# aasaver_v11.net
KiCad netlist of a schematic drawn in EAGLE
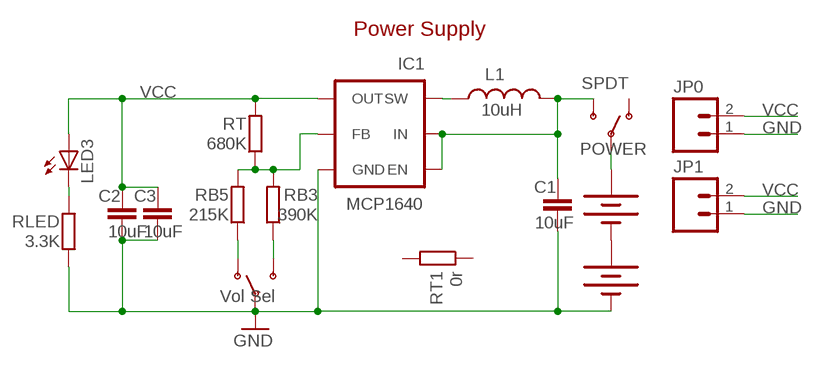
[diagram p0: schematic, sheet 1]

(export (version "E")
  (design (tool "Eeschema 10.0.6"))
  (components
    (comp (ref "AA1")
      (value "BATTERYAA")
      (footprint "eagle-import:BATTERY-AA")
      (libsource (lib "eagle-import") (part "BATTERYAA"))
    )
    (comp (ref "AA2")
      (value "BATTERYAA")
      (footprint "eagle-import:BATTERY-AA")
      (libsource (lib "eagle-import") (part "BATTERYAA"))
    )
    (comp (ref "C1")
      (value "10uF")
      (footprint "eagle-import:C0805")
      (libsource (lib "eagle-import") (part "C-EUC0805"))
    )
    (comp (ref "C2")
      (value "10uF")
      (footprint "eagle-import:C0805")
      (libsource (lib "eagle-import") (part "C-EUC0805"))
    )
    (comp (ref "C3")
      (value "10uF")
      (footprint "eagle-import:C0805")
      (libsource (lib "eagle-import") (part "C-EUC0805"))
    )
    (comp (ref "IC1")
      (value "MCP1640")
      (footprint "eagle-import:TSOT23-6")
      (libsource (lib "eagle-import") (part "MCP1640"))
    )
    (comp (ref "JP0")
      (value "M021X02_NO_SILK")
      (footprint "eagle-import:1X02_NO_SILK")
      (libsource (lib "eagle-import") (part "M021X02_NO_SILK"))
    )
    (comp (ref "JP1")
      (value "M021X02_NO_SILK")
      (footprint "eagle-import:1X02_NO_SILK")
      (libsource (lib "eagle-import") (part "M021X02_NO_SILK"))
    )
    (comp (ref "L1")
      (value "10uH")
      (footprint "eagle-import:INDUCTOR_D45")
      (libsource (lib "eagle-import") (part "INDUCTOR_SMDD45"))
    )
    (comp (ref "LED3")
      (value "0805")
      (footprint "eagle-import:CHIPLED_1206")
      (libsource (lib "eagle-import") (part "LEDCHIPLED_1206"))
    )
    (comp (ref "POWER")
      (value "SPDT")
      (footprint "eagle-import:SWITCH-SPDT-SMD")
      (libsource (lib "eagle-import") (part "SWITCH-SPSTSMD2"))
    )
    (comp (ref "RB3")
      (value "390K")
      (footprint "eagle-import:R0805")
      (libsource (lib "eagle-import") (part "R-EU_R0805"))
    )
    (comp (ref "RB5")
      (value "215K")
      (footprint "eagle-import:R0805")
      (libsource (lib "eagle-import") (part "R-EU_R0805"))
    )
    (comp (ref "RLED")
      (value "3.3K")
      (footprint "eagle-import:R0805")
      (libsource (lib "eagle-import") (part "R-EU_R0805"))
    )
    (comp (ref "RT")
      (value "680K")
      (footprint "eagle-import:R0805")
      (libsource (lib "eagle-import") (part "R-EU_R0805"))
    )
    (comp (ref "RT1")
      (value "0r")
      (footprint "eagle-import:R1206")
      (libsource (lib "eagle-import") (part "R-EU_R1206"))
    )
    (comp (ref "VOL1")
      (value "Vol Sel")
      (footprint "eagle-import:SWITCH-SPDT-SMD")
      (libsource (lib "eagle-import") (part "SWITCH-SPSTSMD2"))
    )
  )
  (nets
    (net (code "1") (name "/VCC") (class "Default")
      (node (ref "C2") (pin "1") (pinfunction "1_1") (pintype "passive"))
      (node (ref "C3") (pin "1") (pinfunction "1_1") (pintype "passive"))
      (node (ref "IC1") (pin "5") (pinfunction "OUT_5") (pintype "passive"))
      (node (ref "JP0") (pin "2") (pinfunction "2_2") (pintype "passive"))
      (node (ref "JP1") (pin "2") (pinfunction "2_2") (pintype "passive"))
      (node (ref "LED3") (pin "A") (pinfunction "A_A") (pintype "passive"))
      (node (ref "RT") (pin "2") (pinfunction "2_2") (pintype "passive"))
    )
    (net (code "2") (name "GND") (class "Default")
      (node (ref "AA2") (pin "GND@1") (pinfunction "-_GND@1") (pintype "power_in"))
      (node (ref "C1") (pin "2") (pinfunction "2_2") (pintype "passive"))
      (node (ref "C2") (pin "2") (pinfunction "2_2") (pintype "passive"))
      (node (ref "C3") (pin "2") (pinfunction "2_2") (pintype "passive"))
      (node (ref "IC1") (pin "2") (pinfunction "GND_2") (pintype "input"))
      (node (ref "JP0") (pin "1") (pinfunction "1_1") (pintype "passive"))
      (node (ref "JP1") (pin "1") (pinfunction "1_1") (pintype "passive"))
      (node (ref "RLED") (pin "1") (pinfunction "1_1") (pintype "passive"))
      (node (ref "VOL1") (pin "2") (pinfunction "P_2") (pintype "passive"))
    )
    (net (code "3") (name "Net-(AA1-+)") (class "Default")
      (node (ref "AA1") (pin "PWR@1") (pinfunction "+_PWR@1") (pintype "power_in"))
      (node (ref "POWER") (pin "2") (pinfunction "P_2") (pintype "passive"))
    )
    (net (code "4") (name "Net-(AA1--)") (class "Default")
      (node (ref "AA1") (pin "GND@1") (pinfunction "-_GND@1") (pintype "power_in"))
      (node (ref "AA2") (pin "PWR@1") (pinfunction "+_PWR@1") (pintype "power_in"))
    )
    (net (code "5") (name "Net-(IC1-EN)") (class "Default")
      (node (ref "C1") (pin "1") (pinfunction "1_1") (pintype "passive"))
      (node (ref "IC1") (pin "3") (pinfunction "EN_3") (pintype "input"))
      (node (ref "IC1") (pin "6") (pinfunction "IN_6") (pintype "input"))
      (node (ref "L1") (pin "P$1") (pinfunction "1_P$1") (pintype "passive"))
      (node (ref "POWER") (pin "3") (pinfunction "S_3") (pintype "passive"))
    )
    (net (code "6") (name "Net-(IC1-FB)") (class "Default")
      (node (ref "IC1") (pin "4") (pinfunction "FB_4") (pintype "input"))
      (node (ref "RB3") (pin "2") (pinfunction "2_2") (pintype "passive"))
      (node (ref "RB5") (pin "2") (pinfunction "2_2") (pintype "passive"))
      (node (ref "RT") (pin "1") (pinfunction "1_1") (pintype "passive"))
    )
    (net (code "7") (name "Net-(IC1-SW)") (class "Default")
      (node (ref "IC1") (pin "1") (pinfunction "SW_1") (pintype "output"))
      (node (ref "L1") (pin "P$2") (pinfunction "2_P$2") (pintype "passive"))
    )
    (net (code "8") (name "Net-(LED3-PadC)") (class "Default")
      (node (ref "LED3") (pin "C") (pinfunction "C_C") (pintype "passive"))
      (node (ref "RLED") (pin "2") (pinfunction "2_2") (pintype "passive"))
    )
    (net (code "9") (name "Net-(VOL1-O)") (class "Default")
      (node (ref "RB5") (pin "1") (pinfunction "1_1") (pintype "passive"))
      (node (ref "VOL1") (pin "1") (pinfunction "O_1") (pintype "passive"))
    )
    (net (code "10") (name "Net-(VOL1-S)") (class "Default")
      (node (ref "RB3") (pin "1") (pinfunction "1_1") (pintype "passive"))
      (node (ref "VOL1") (pin "3") (pinfunction "S_3") (pintype "passive"))
    )
    (net (code "11") (name "unconnected-(POWER-O-Pad1)") (class "Default")
      (node (ref "POWER") (pin "1") (pinfunction "O_1") (pintype "passive"))
    )
    (net (code "12") (name "unconnected-(RT1-Pad1)") (class "Default")
      (node (ref "RT1") (pin "1") (pinfunction "1_1") (pintype "passive"))
    )
    (net (code "13") (name "unconnected-(RT1-Pad2)") (class "Default")
      (node (ref "RT1") (pin "2") (pinfunction "2_2") (pintype "passive"))
    )
  )
)
